# Galileo_Control_Board.net
KiCad netlist of a schematic drawn in Altium Designer
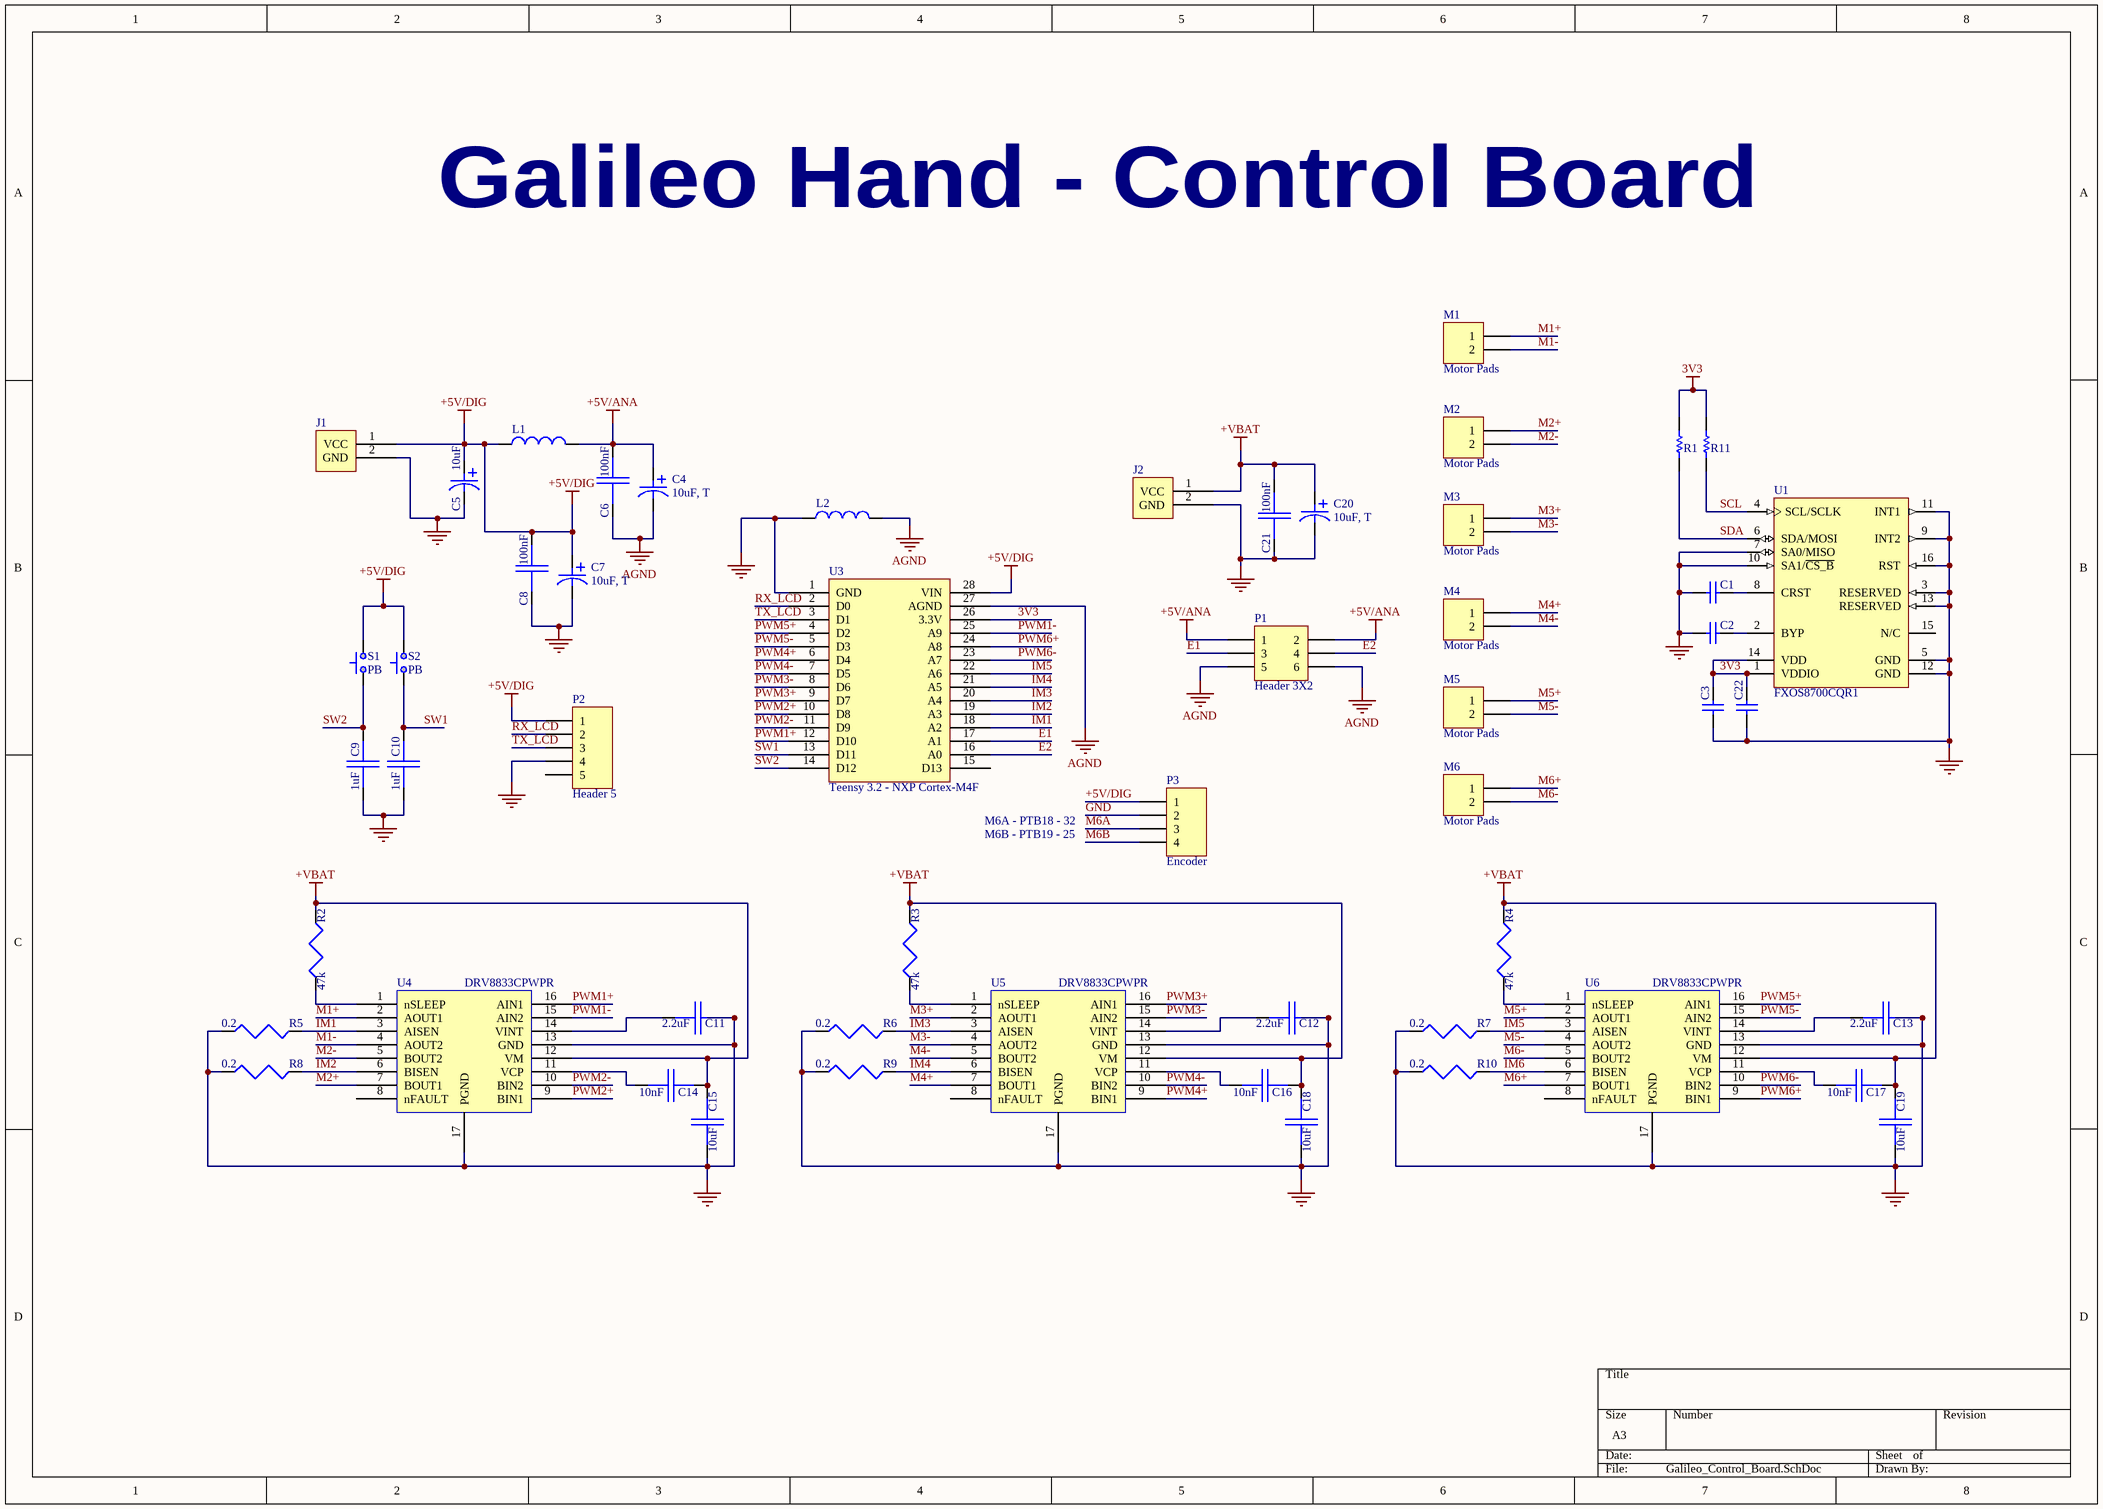
[diagram p0: Galileo_Control_Board.SchDoc]

(export (version "E")
  (design (tool "Eeschema 10.0.6"))
  (components
    (comp (ref "C1")
      (value "GRM155R71C104KA88J")
      (footprint "CAPC1005X55X25LL05T10")
      (fields (field (name "MANUFACTURER") "Murata"))
      (libsource (lib "Altium Content Vault") (part "CMP-2008-03928-1"))
    )
    (comp (ref "C2")
      (value "GRM155R71C104KA88J")
      (footprint "CAPC1005X55X25LL05T10")
      (fields (field (name "MANUFACTURER") "Murata"))
      (libsource (lib "Altium Content Vault") (part "CMP-2008-03928-1"))
    )
    (comp (ref "C3")
      (value "GRM155R60J475ME47D")
      (footprint "CAPC1005X55X25NL05T10")
      (fields (field (name "MANUFACTURER") "Murata"))
      (libsource (lib "Altium Content Vault") (part "CAP"))
    )
    (comp (ref "C4")
      (value "10uF, T")
      (footprint "C1206")
      (description "CAP TANT 10UF 20V 10% 2413")
      (fields
        (field (name "MANUFACTURER") "Kemet")
        (field (name "MANUFACTURER PART NUMBER") "TCJA106M025R0150")
      )
      (libsource (lib "Control") (part "T491C106K020AT"))
    )
    (comp (ref "C5")
      (value "10uF")
      (footprint "CSVB")
      (description "CAP ALUM 10UF 20% 25V SMD")
      (fields
        (field (name "MANUFACTURER") "Panasonic Electronic Components")
        (field (name "MANUFACTURER PART NUMBER") "EEE-1EA100WR")
      )
      (libsource (lib "Control") (part "EEE-1EA100WR"))
    )
    (comp (ref "C6")
      (value "100nF")
      (footprint "C0603")
      (description "CAP CER 0.1UF 25V X7R 0603")
      (fields
        (field (name "MANUFACTURER") "Murata Electronics North America")
        (field (name "MANUFACTURER PART NUMBER") "GRM188R71E104KA01D")
      )
      (libsource (lib "EMG") (part "GRM188R71E104KA01D"))
    )
    (comp (ref "C7")
      (value "10uF, T")
      (footprint "C1206")
      (description "CAP TANT 10UF 20V 10% 2413")
      (fields
        (field (name "MANUFACTURER") "Kemet")
        (field (name "MANUFACTURER PART NUMBER") "TCJA106M025R0150")
      )
      (libsource (lib "Control") (part "T491C106K020AT"))
    )
    (comp (ref "C8")
      (value "100nF")
      (footprint "C0603")
      (description "CAP CER 0.1UF 25V X7R 0603")
      (fields
        (field (name "MANUFACTURER") "Murata Electronics North America")
        (field (name "MANUFACTURER PART NUMBER") "GRM188R71E104KA01D")
      )
      (libsource (lib "EMG") (part "GRM188R71E104KA01D"))
    )
    (comp (ref "C9")
      (value "1uF")
      (footprint "C0603")
      (description "CAP CER 1UF 25V X5R 0603")
      (fields
        (field (name "MANUFACTURER") "Murata Electronics North America")
        (field (name "MANUFACTURER PART NUMBER") "GRM188R61E105KA12D")
      )
      (libsource (lib "EMG") (part "GRM188R61E105KA12D"))
    )
    (comp (ref "C10")
      (value "1uF")
      (footprint "C0603")
      (description "CAP CER 1UF 25V X5R 0603")
      (fields
        (field (name "MANUFACTURER") "Murata Electronics North America")
        (field (name "MANUFACTURER PART NUMBER") "GRM188R61E105KA12D")
      )
      (libsource (lib "EMG") (part "GRM188R61E105KA12D"))
    )
    (comp (ref "C11")
      (value "2.2uF")
      (footprint "C0603")
      (description "CAP CER 2.2UF 6.3V X5R 0603")
      (fields
        (field (name "MANUFACTURER") "AVX Corporation")
        (field (name "MANUFACTURER PART NUMBER") "06036D225KAT2A")
      )
      (libsource (lib "Galileo_Control_Board") (part "06036D225KAT2A"))
    )
    (comp (ref "C12")
      (value "2.2uF")
      (footprint "C0603")
      (description "CAP CER 2.2UF 6.3V X5R 0603")
      (fields
        (field (name "MANUFACTURER") "AVX Corporation")
        (field (name "MANUFACTURER PART NUMBER") "06036D225KAT2A")
      )
      (libsource (lib "Galileo_Control_Board") (part "06036D225KAT2A"))
    )
    (comp (ref "C13")
      (value "2.2uF")
      (footprint "C0603")
      (description "CAP CER 2.2UF 6.3V X5R 0603")
      (fields
        (field (name "MANUFACTURER") "AVX Corporation")
        (field (name "MANUFACTURER PART NUMBER") "06036D225KAT2A")
      )
      (libsource (lib "Galileo_Control_Board") (part "06036D225KAT2A"))
    )
    (comp (ref "C14")
      (value "10nF")
      (footprint "C0603")
      (description "CAP CER 10000PF 16V X7R 0603")
      (fields
        (field (name "MANUFACTURER") "Kemet")
        (field (name "MANUFACTURER PART NUMBER") "C0603C103K4RACTU")
      )
      (libsource (lib "Galileo_Control_Board") (part "C0603C103K4RACTU"))
    )
    (comp (ref "C15")
      (value "10uF")
      (footprint "C0603")
      (description "CAP CER 10UF 25V X5R 0603")
      (fields
        (field (name "MANUFACTURER") "Murata Electronics North America")
        (field (name "MANUFACTURER PART NUMBER") "GRT188R61E106ME13D")
      )
      (libsource (lib "Galileo_Control_Board") (part "GRT188R61E106ME13D"))
    )
    (comp (ref "C16")
      (value "10nF")
      (footprint "C0603")
      (description "CAP CER 10000PF 16V X7R 0603")
      (fields
        (field (name "MANUFACTURER") "Kemet")
        (field (name "MANUFACTURER PART NUMBER") "C0603C103K4RACTU")
      )
      (libsource (lib "Galileo_Control_Board") (part "C0603C103K4RACTU"))
    )
    (comp (ref "C17")
      (value "10nF")
      (footprint "C0603")
      (description "CAP CER 10000PF 16V X7R 0603")
      (fields
        (field (name "MANUFACTURER") "Kemet")
        (field (name "MANUFACTURER PART NUMBER") "C0603C103K4RACTU")
      )
      (libsource (lib "Galileo_Control_Board") (part "C0603C103K4RACTU"))
    )
    (comp (ref "C18")
      (value "10uF")
      (footprint "C0603")
      (description "CAP CER 10UF 25V X5R 0603")
      (fields
        (field (name "MANUFACTURER") "Murata Electronics North America")
        (field (name "MANUFACTURER PART NUMBER") "GRT188R61E106ME13D")
      )
      (libsource (lib "Galileo_Control_Board") (part "GRT188R61E106ME13D"))
    )
    (comp (ref "C19")
      (value "10uF")
      (footprint "C0603")
      (description "CAP CER 10UF 25V X5R 0603")
      (fields
        (field (name "MANUFACTURER") "Murata Electronics North America")
        (field (name "MANUFACTURER PART NUMBER") "GRT188R61E106ME13D")
      )
      (libsource (lib "Galileo_Control_Board") (part "GRT188R61E106ME13D"))
    )
    (comp (ref "C20")
      (value "10uF, T")
      (footprint "C1206")
      (description "CAP TANT 10UF 20V 10% 2413")
      (fields
        (field (name "MANUFACTURER") "Kemet")
        (field (name "MANUFACTURER PART NUMBER") "TCJA106M025R0150")
      )
      (libsource (lib "Control") (part "T491C106K020AT"))
    )
    (comp (ref "C21")
      (value "100nF")
      (footprint "C0603")
      (description "CAP CER 0.1UF 25V X7R 0603")
      (fields
        (field (name "MANUFACTURER") "Murata Electronics North America")
        (field (name "MANUFACTURER PART NUMBER") "GRM188R71E104KA01D")
      )
      (libsource (lib "EMG") (part "GRM188R71E104KA01D"))
    )
    (comp (ref "C22")
      (value "GRM155R71C104KA88J")
      (footprint "CAPC1005X55X25LL05T10")
      (fields (field (name "MANUFACTURER") "Murata"))
      (libsource (lib "Altium Content Vault") (part "CMP-2008-03928-1"))
    )
    (comp (ref "J1")
      (value "TERMINAL BLOCK  2POS 3.5MM")
      (footprint "2POS3.5mm")
      (description "CONN TERMINAL BLOCK 2POS 3.5MM")
      (fields
        (field (name "MANUFACTURER") "Molex, LLC")
        (field (name "MANUFACTURER PART NUMBER") "0393570002")
      )
      (libsource (lib "Control") (part "0393570002"))
    )
    (comp (ref "J2")
      (value "TERMINAL BLOCK  2POS 3.5MM")
      (footprint "2POS3.5mm")
      (description "CONN TERMINAL BLOCK 2POS 3.5MM")
      (fields
        (field (name "MANUFACTURER") "Molex, LLC")
        (field (name "MANUFACTURER PART NUMBER") "0393570002")
      )
      (libsource (lib "Control") (part "0393570002"))
    )
    (comp (ref "L1")
      (value "EMI FILTER BED")
      (footprint "R0603")
      (description "FERRITE BEAD 470 OHM 0603")
      (fields
        (field (name "MANUFACTURER") "Murata Electronics North America")
        (field (name "MANUFACTURER PART NUMBER") "BLM18PG471SN1D")
      )
      (libsource (lib "Control") (part "BLM18PG471SN1D"))
    )
    (comp (ref "L2")
      (value "EMI FILTER BED")
      (footprint "R0603")
      (description "FERRITE BEAD 470 OHM 0603")
      (fields
        (field (name "MANUFACTURER") "Murata Electronics North America")
        (field (name "MANUFACTURER PART NUMBER") "BLM18PG471SN1D")
      )
      (libsource (lib "Control") (part "BLM18PG471SN1D"))
    )
    (comp (ref "M1")
      (value "Motor Pads")
      (footprint "HDR1X2")
      (description "Header, 2-Pin")
      (fields (field (name "PUBLISHER") "Altium Limited"))
      (libsource (lib "Miscellaneous Connectors") (part "Header 2"))
    )
    (comp (ref "M2")
      (value "Motor Pads")
      (footprint "HDR1X2")
      (description "Header, 2-Pin")
      (fields (field (name "PUBLISHER") "Altium Limited"))
      (libsource (lib "Miscellaneous Connectors") (part "Header 2"))
    )
    (comp (ref "M3")
      (value "Motor Pads")
      (footprint "HDR1X2")
      (description "Header, 2-Pin")
      (fields (field (name "PUBLISHER") "Altium Limited"))
      (libsource (lib "Miscellaneous Connectors") (part "Header 2"))
    )
    (comp (ref "M4")
      (value "Motor Pads")
      (footprint "HDR1X2")
      (description "Header, 2-Pin")
      (fields (field (name "PUBLISHER") "Altium Limited"))
      (libsource (lib "Miscellaneous Connectors") (part "Header 2"))
    )
    (comp (ref "M5")
      (value "Motor Pads")
      (footprint "HDR1X2")
      (description "Header, 2-Pin")
      (fields (field (name "PUBLISHER") "Altium Limited"))
      (libsource (lib "Miscellaneous Connectors") (part "Header 2"))
    )
    (comp (ref "M6")
      (value "Motor Pads")
      (footprint "HDR1X2")
      (description "Header, 2-Pin")
      (fields (field (name "PUBLISHER") "Altium Limited"))
      (libsource (lib "Miscellaneous Connectors") (part "Header 2"))
    )
    (comp (ref "P1")
      (value "Header 3X2")
      (footprint "HDR2X3")
      (description "Header, 3-Pin, Dual row")
      (fields (field (name "PUBLISHER") "Altium Limited"))
      (libsource (lib "Miscellaneous Connectors") (part "Header 3X2"))
    )
    (comp (ref "P2")
      (value "Header 5")
      (footprint "HDR1X5")
      (description "Header, 5-Pin")
      (fields (field (name "PUBLISHER") "Altium Limited"))
      (libsource (lib "Miscellaneous Connectors") (part "Header 5"))
    )
    (comp (ref "P3")
      (value "Encoder")
      (footprint "HDR1X4")
      (description "Header, 4-Pin")
      (fields (field (name "PUBLISHER") "Altium Limited"))
      (libsource (lib "Miscellaneous Connectors") (part "Header 4"))
    )
    (comp (ref "R1")
      (value "ERA-2AED472X")
      (footprint "RESC1005X40X25NL10T10")
      (fields (field (name "MANUFACTURER") "Panasonic"))
      (libsource (lib "Altium Content Vault") (part "CMP-2002-05861-1"))
    )
    (comp (ref "R2")
      (value "47k")
      (footprint "R0603")
      (description "RES SMD 47K OHM 1% 1/10W 0603")
      (fields
        (field (name "MANUFACTURER") "Panasonic Electronic Components")
        (field (name "MANUFACTURER PART NUMBER") "ERJ-3EKF4702V")
      )
      (libsource (lib "Galileo_Control_Board") (part "ERJ-3EKF4702V"))
    )
    (comp (ref "R3")
      (value "47k")
      (footprint "R0603")
      (description "RES SMD 47K OHM 1% 1/10W 0603")
      (fields
        (field (name "MANUFACTURER") "Panasonic Electronic Components")
        (field (name "MANUFACTURER PART NUMBER") "ERJ-3EKF4702V")
      )
      (libsource (lib "Galileo_Control_Board") (part "ERJ-3EKF4702V"))
    )
    (comp (ref "R4")
      (value "47k")
      (footprint "R0603")
      (description "RES SMD 47K OHM 1% 1/10W 0603")
      (fields
        (field (name "MANUFACTURER") "Panasonic Electronic Components")
        (field (name "MANUFACTURER PART NUMBER") "ERJ-3EKF4702V")
      )
      (libsource (lib "Galileo_Control_Board") (part "ERJ-3EKF4702V"))
    )
    (comp (ref "R5")
      (value "0.2")
      (footprint "R1206")
      (description "RES SMD 0.2 OHM 5% 1/2W 1206")
      (fields
        (field (name "MANUFACTURER") "Panasonic Electronic Components")
        (field (name "MANUFACTURER PART NUMBER") "ERJ-8BSJR20V")
      )
      (libsource (lib "Galileo_Control_Board") (part "ERJ-8BSJR20V"))
    )
    (comp (ref "R6")
      (value "0.2")
      (footprint "R1206")
      (description "RES SMD 0.2 OHM 5% 1/2W 1206")
      (fields
        (field (name "MANUFACTURER") "Panasonic Electronic Components")
        (field (name "MANUFACTURER PART NUMBER") "ERJ-8BSJR20V")
      )
      (libsource (lib "Galileo_Control_Board") (part "ERJ-8BSJR20V"))
    )
    (comp (ref "R7")
      (value "0.2")
      (footprint "R1206")
      (description "RES SMD 0.2 OHM 5% 1/2W 1206")
      (fields
        (field (name "MANUFACTURER") "Panasonic Electronic Components")
        (field (name "MANUFACTURER PART NUMBER") "ERJ-8BSJR20V")
      )
      (libsource (lib "Galileo_Control_Board") (part "ERJ-8BSJR20V"))
    )
    (comp (ref "R8")
      (value "0.2")
      (footprint "R1206")
      (description "RES SMD 0.2 OHM 5% 1/2W 1206")
      (fields
        (field (name "MANUFACTURER") "Panasonic Electronic Components")
        (field (name "MANUFACTURER PART NUMBER") "ERJ-8BSJR20V")
      )
      (libsource (lib "Galileo_Control_Board") (part "ERJ-8BSJR20V"))
    )
    (comp (ref "R9")
      (value "0.2")
      (footprint "R1206")
      (description "RES SMD 0.2 OHM 5% 1/2W 1206")
      (fields
        (field (name "MANUFACTURER") "Panasonic Electronic Components")
        (field (name "MANUFACTURER PART NUMBER") "ERJ-8BSJR20V")
      )
      (libsource (lib "Galileo_Control_Board") (part "ERJ-8BSJR20V"))
    )
    (comp (ref "R10")
      (value "0.2")
      (footprint "R1206")
      (description "RES SMD 0.2 OHM 5% 1/2W 1206")
      (fields
        (field (name "MANUFACTURER") "Panasonic Electronic Components")
        (field (name "MANUFACTURER PART NUMBER") "ERJ-8BSJR20V")
      )
      (libsource (lib "Galileo_Control_Board") (part "ERJ-8BSJR20V"))
    )
    (comp (ref "R11")
      (value "ERA-2AED472X")
      (footprint "RESC1005X40X25NL10T10")
      (fields (field (name "MANUFACTURER") "Panasonic"))
      (libsource (lib "Altium Content Vault") (part "CMP-2002-05861-1"))
    )
    (comp (ref "S1")
      (value "PB")
      (footprint "SW")
      (description "SWITCH PUSH SPST-NO 0.1A 32V")
      (fields
        (field (name "MANUFACTURER") "C&K Components")
        (field (name "MANUFACTURER PART NUMBER") "D6C90 F1 LFS")
      )
      (libsource (lib "Control") (part "D6C90 F1 LFS"))
    )
    (comp (ref "S2")
      (value "PB")
      (footprint "SW")
      (description "SWITCH PUSH SPST-NO 0.1A 32V")
      (fields
        (field (name "MANUFACTURER") "C&K Components")
        (field (name "MANUFACTURER PART NUMBER") "D6C90 F1 LFS")
      )
      (libsource (lib "Control") (part "D6C90 F1 LFS"))
    )
    (comp (ref "U1")
      (value "FXOS8700CQR1")
      (footprint "FREE-QFN-16-3000X3000DE_V")
      (fields (field (name "MANUFACTURER") "Freescale"))
      (libsource (lib "Altium Content Vault") (part "FREE-FXOS8700CQR1-16"))
    )
    (comp (ref "U3")
      (value "Teensy 3.2 - NXP Cortex-M4F")
      (footprint "DIP28")
      (fields
        (field (name "MANUFACTURER") "SparkFun Electronics")
        (field (name "MANUFACTURER PART NUMBER") "DEV-13305")
      )
      (libsource (lib "Galileo_Control_Board_Library") (part "Teensy"))
    )
    (comp (ref "U4")
      (value "DRV8833CPWPR")
      (footprint "SOP16")
      (description "IC MOTOR DRIVER PAR")
      (fields (field (name "MANUFACTURER") "Texas Instruments"))
      (libsource (lib "Galileo_Control_Board") (part "DRV8833CPWPR"))
    )
    (comp (ref "U5")
      (value "DRV8833CPWPR")
      (footprint "SOP16")
      (description "IC MOTOR DRIVER PAR")
      (fields (field (name "MANUFACTURER") "Texas Instruments"))
      (libsource (lib "Galileo_Control_Board") (part "DRV8833CPWPR"))
    )
    (comp (ref "U6")
      (value "DRV8833CPWPR")
      (footprint "SOP16")
      (description "IC MOTOR DRIVER PAR")
      (fields (field (name "MANUFACTURER") "Texas Instruments"))
      (libsource (lib "Galileo_Control_Board") (part "DRV8833CPWPR"))
    )
  )
  (nets
    (net (code "1") (name "+5V{slash}ANA") (class "Default")
      (node (ref "C4") (pin "1") (pinfunction "1_1") (pintype "passive"))
      (node (ref "C6") (pin "2") (pinfunction "2_2") (pintype "passive"))
      (node (ref "L1") (pin "2") (pinfunction "2_2") (pintype "passive"))
      (node (ref "P1") (pin "1") (pinfunction "1_1") (pintype "passive"))
      (node (ref "P1") (pin "2") (pinfunction "2_2") (pintype "passive"))
    )
    (net (code "2") (name "+5V{slash}DIG") (class "Default")
      (node (ref "C5") (pin "1") (pinfunction "1_1") (pintype "passive"))
      (node (ref "C7") (pin "1") (pinfunction "1_1") (pintype "passive"))
      (node (ref "C8") (pin "2") (pinfunction "2_2") (pintype "passive"))
      (node (ref "J1") (pin "1") (pinfunction "VCC_1") (pintype "passive"))
      (node (ref "L1") (pin "1") (pinfunction "1_1") (pintype "passive"))
      (node (ref "P2") (pin "1") (pinfunction "1_1") (pintype "passive"))
      (node (ref "P3") (pin "1") (pinfunction "1_1") (pintype "passive"))
      (node (ref "S1") (pin "2") (pinfunction "2_2") (pintype "passive"))
      (node (ref "S2") (pin "2") (pinfunction "2_2") (pintype "passive"))
      (node (ref "U3") (pin "28") (pinfunction "VIN_28") (pintype "passive"))
    )
    (net (code "3") (name "+VBAT") (class "Default")
      (node (ref "C14") (pin "2") (pinfunction "2_2") (pintype "passive"))
      (node (ref "C15") (pin "2") (pinfunction "2_2") (pintype "passive"))
      (node (ref "C16") (pin "2") (pinfunction "2_2") (pintype "passive"))
      (node (ref "C17") (pin "2") (pinfunction "2_2") (pintype "passive"))
      (node (ref "C18") (pin "2") (pinfunction "2_2") (pintype "passive"))
      (node (ref "C19") (pin "2") (pinfunction "2_2") (pintype "passive"))
      (node (ref "C20") (pin "1") (pinfunction "1_1") (pintype "passive"))
      (node (ref "C21") (pin "2") (pinfunction "2_2") (pintype "passive"))
      (node (ref "J2") (pin "1") (pinfunction "VCC_1") (pintype "passive"))
      (node (ref "R2") (pin "2") (pinfunction "2_2") (pintype "passive"))
      (node (ref "R3") (pin "2") (pinfunction "2_2") (pintype "passive"))
      (node (ref "R4") (pin "2") (pinfunction "2_2") (pintype "passive"))
      (node (ref "U4") (pin "12") (pinfunction "VM_12") (pintype "passive"))
      (node (ref "U5") (pin "12") (pinfunction "VM_12") (pintype "passive"))
      (node (ref "U6") (pin "12") (pinfunction "VM_12") (pintype "passive"))
    )
    (net (code "4") (name "/E1") (class "Default")
      (node (ref "P1") (pin "3") (pinfunction "3_3") (pintype "passive"))
      (node (ref "U3") (pin "17") (pinfunction "A1_17") (pintype "passive"))
    )
    (net (code "5") (name "/E2") (class "Default")
      (node (ref "P1") (pin "4") (pinfunction "4_4") (pintype "passive"))
      (node (ref "U3") (pin "16") (pinfunction "A0_16") (pintype "passive"))
    )
    (net (code "6") (name "/IM1") (class "Default")
      (node (ref "R5") (pin "2") (pinfunction "2_2") (pintype "passive"))
      (node (ref "U3") (pin "18") (pinfunction "A2_18") (pintype "passive"))
      (node (ref "U4") (pin "3") (pinfunction "AISEN_3") (pintype "passive"))
    )
    (net (code "7") (name "/IM2") (class "Default")
      (node (ref "R8") (pin "2") (pinfunction "2_2") (pintype "passive"))
      (node (ref "U3") (pin "19") (pinfunction "A3_19") (pintype "passive"))
      (node (ref "U4") (pin "6") (pinfunction "BISEN_6") (pintype "passive"))
    )
    (net (code "8") (name "/IM3") (class "Default")
      (node (ref "R6") (pin "2") (pinfunction "2_2") (pintype "passive"))
      (node (ref "U3") (pin "20") (pinfunction "A4_20") (pintype "passive"))
      (node (ref "U5") (pin "3") (pinfunction "AISEN_3") (pintype "passive"))
    )
    (net (code "9") (name "/IM4") (class "Default")
      (node (ref "R9") (pin "2") (pinfunction "2_2") (pintype "passive"))
      (node (ref "U3") (pin "21") (pinfunction "A5_21") (pintype "passive"))
      (node (ref "U5") (pin "6") (pinfunction "BISEN_6") (pintype "passive"))
    )
    (net (code "10") (name "/IM5") (class "Default")
      (node (ref "R7") (pin "2") (pinfunction "2_2") (pintype "passive"))
      (node (ref "U3") (pin "22") (pinfunction "A6_22") (pintype "passive"))
      (node (ref "U6") (pin "3") (pinfunction "AISEN_3") (pintype "passive"))
    )
    (net (code "11") (name "/IM6") (class "Default")
      (node (ref "R10") (pin "2") (pinfunction "2_2") (pintype "passive"))
      (node (ref "U6") (pin "6") (pinfunction "BISEN_6") (pintype "passive"))
    )
    (net (code "12") (name "/M1+") (class "Default")
      (node (ref "M1") (pin "1") (pinfunction "1_1") (pintype "passive"))
      (node (ref "U4") (pin "2") (pinfunction "AOUT1_2") (pintype "passive"))
    )
    (net (code "13") (name "/M1-") (class "Default")
      (node (ref "M1") (pin "2") (pinfunction "2_2") (pintype "passive"))
      (node (ref "U4") (pin "4") (pinfunction "AOUT2_4") (pintype "passive"))
    )
    (net (code "14") (name "/M2+") (class "Default")
      (node (ref "M2") (pin "1") (pinfunction "1_1") (pintype "passive"))
      (node (ref "U4") (pin "7") (pinfunction "BOUT1_7") (pintype "passive"))
    )
    (net (code "15") (name "/M2-") (class "Default")
      (node (ref "M2") (pin "2") (pinfunction "2_2") (pintype "passive"))
      (node (ref "U4") (pin "5") (pinfunction "BOUT2_5") (pintype "passive"))
    )
    (net (code "16") (name "/M3+") (class "Default")
      (node (ref "M3") (pin "1") (pinfunction "1_1") (pintype "passive"))
      (node (ref "U5") (pin "2") (pinfunction "AOUT1_2") (pintype "passive"))
    )
    (net (code "17") (name "/M3-") (class "Default")
      (node (ref "M3") (pin "2") (pinfunction "2_2") (pintype "passive"))
      (node (ref "U5") (pin "4") (pinfunction "AOUT2_4") (pintype "passive"))
    )
    (net (code "18") (name "/M4+") (class "Default")
      (node (ref "M4") (pin "1") (pinfunction "1_1") (pintype "passive"))
      (node (ref "U5") (pin "7") (pinfunction "BOUT1_7") (pintype "passive"))
    )
    (net (code "19") (name "/M4-") (class "Default")
      (node (ref "M4") (pin "2") (pinfunction "2_2") (pintype "passive"))
      (node (ref "U5") (pin "5") (pinfunction "BOUT2_5") (pintype "passive"))
    )
    (net (code "20") (name "/M5+") (class "Default")
      (node (ref "M5") (pin "1") (pinfunction "1_1") (pintype "passive"))
      (node (ref "U6") (pin "2") (pinfunction "AOUT1_2") (pintype "passive"))
    )
    (net (code "21") (name "/M5-") (class "Default")
      (node (ref "M5") (pin "2") (pinfunction "2_2") (pintype "passive"))
      (node (ref "U6") (pin "4") (pinfunction "AOUT2_4") (pintype "passive"))
    )
    (net (code "22") (name "/M6+") (class "Default")
      (node (ref "M6") (pin "1") (pinfunction "1_1") (pintype "passive"))
      (node (ref "U6") (pin "7") (pinfunction "BOUT1_7") (pintype "passive"))
    )
    (net (code "23") (name "/M6-") (class "Default")
      (node (ref "M6") (pin "2") (pinfunction "2_2") (pintype "passive"))
      (node (ref "U6") (pin "5") (pinfunction "BOUT2_5") (pintype "passive"))
    )
    (net (code "24") (name "/M6A") (class "Default")
      (node (ref "P3") (pin "3") (pinfunction "3_3") (pintype "passive"))
    )
    (net (code "25") (name "/M6B") (class "Default")
      (node (ref "P3") (pin "4") (pinfunction "4_4") (pintype "passive"))
    )
    (net (code "26") (name "/PWM1+") (class "Default")
      (node (ref "U3") (pin "12") (pinfunction "D10_12") (pintype "passive"))
      (node (ref "U4") (pin "16") (pinfunction "AIN1_16") (pintype "passive"))
    )
    (net (code "27") (name "/PWM1-") (class "Default")
      (node (ref "U3") (pin "25") (pinfunction "A9_25") (pintype "passive"))
      (node (ref "U4") (pin "15") (pinfunction "AIN2_15") (pintype "passive"))
    )
    (net (code "28") (name "/PWM2+") (class "Default")
      (node (ref "U3") (pin "10") (pinfunction "D8_10") (pintype "passive"))
      (node (ref "U4") (pin "9") (pinfunction "BIN1_9") (pintype "passive"))
    )
    (net (code "29") (name "/PWM2-") (class "Default")
      (node (ref "U3") (pin "11") (pinfunction "D9_11") (pintype "passive"))
      (node (ref "U4") (pin "10") (pinfunction "BIN2_10") (pintype "passive"))
    )
    (net (code "30") (name "/PWM3+") (class "Default")
      (node (ref "U3") (pin "9") (pinfunction "D7_9") (pintype "passive"))
      (node (ref "U5") (pin "16") (pinfunction "AIN1_16") (pintype "passive"))
    )
    (net (code "31") (name "/PWM3-") (class "Default")
      (node (ref "U3") (pin "8") (pinfunction "D6_8") (pintype "passive"))
      (node (ref "U5") (pin "15") (pinfunction "AIN2_15") (pintype "passive"))
    )
    (net (code "32") (name "/PWM4+") (class "Default")
      (node (ref "U3") (pin "6") (pinfunction "D4_6") (pintype "passive"))
      (node (ref "U5") (pin "9") (pinfunction "BIN1_9") (pintype "passive"))
    )
    (net (code "33") (name "/PWM4-") (class "Default")
      (node (ref "U3") (pin "7") (pinfunction "D5_7") (pintype "passive"))
      (node (ref "U5") (pin "10") (pinfunction "BIN2_10") (pintype "passive"))
    )
    (net (code "34") (name "/PWM5+") (class "Default")
      (node (ref "U3") (pin "4") (pinfunction "D2_4") (pintype "passive"))
      (node (ref "U6") (pin "16") (pinfunction "AIN1_16") (pintype "passive"))
    )
    (net (code "35") (name "/PWM5-") (class "Default")
      (node (ref "U3") (pin "5") (pinfunction "D3_5") (pintype "passive"))
      (node (ref "U6") (pin "15") (pinfunction "AIN2_15") (pintype "passive"))
    )
    (net (code "36") (name "/PWM6+") (class "Default")
      (node (ref "U3") (pin "24") (pinfunction "A8_24") (pintype "passive"))
      (node (ref "U6") (pin "9") (pinfunction "BIN1_9") (pintype "passive"))
    )
    (net (code "37") (name "/PWM6-") (class "Default")
      (node (ref "U3") (pin "23") (pinfunction "A7_23") (pintype "passive"))
      (node (ref "U6") (pin "10") (pinfunction "BIN2_10") (pintype "passive"))
    )
    (net (code "38") (name "/RX_LCD") (class "Default")
      (node (ref "P2") (pin "2") (pinfunction "2_2") (pintype "passive"))
      (node (ref "U3") (pin "2") (pinfunction "D0_2") (pintype "passive"))
    )
    (net (code "39") (name "/SCL") (class "Default")
      (node (ref "R11") (pin "1") (pinfunction "1_1") (pintype "passive"))
      (node (ref "U1") (pin "4") (pinfunction "SCL/SCLK_4") (pintype "input"))
    )
    (net (code "40") (name "/SDA") (class "Default")
      (node (ref "R1") (pin "1") (pinfunction "1_1") (pintype "passive"))
      (node (ref "U1") (pin "6") (pinfunction "SDA/MOSI_6") (pintype "bidirectional"))
    )
    (net (code "41") (name "/SW1") (class "Default")
      (node (ref "C10") (pin "2") (pinfunction "2_2") (pintype "passive"))
      (node (ref "S2") (pin "1") (pinfunction "1_1") (pintype "passive"))
      (node (ref "U3") (pin "13") (pinfunction "D11_13") (pintype "passive"))
    )
    (net (code "42") (name "/SW2") (class "Default")
      (node (ref "C9") (pin "2") (pinfunction "2_2") (pintype "passive"))
      (node (ref "S1") (pin "1") (pinfunction "1_1") (pintype "passive"))
      (node (ref "U3") (pin "14") (pinfunction "D12_14") (pintype "passive"))
    )
    (net (code "43") (name "/TX_LCD") (class "Default")
      (node (ref "P2") (pin "3") (pinfunction "3_3") (pintype "passive"))
      (node (ref "U3") (pin "3") (pinfunction "D1_3") (pintype "passive"))
    )
    (net (code "44") (name "3V3") (class "Default")
      (node (ref "C22") (pin "2") (pinfunction "2_2") (pintype "passive"))
      (node (ref "C3") (pin "2") (pinfunction "2_2") (pintype "passive"))
      (node (ref "R1") (pin "2") (pinfunction "2_2") (pintype "passive"))
      (node (ref "R11") (pin "2") (pinfunction "2_2") (pintype "passive"))
      (node (ref "U1") (pin "1") (pinfunction "VDDIO_1") (pintype "power_in"))
      (node (ref "U1") (pin "14") (pinfunction "VDD_14") (pintype "power_in"))
      (node (ref "U3") (pin "26") (pinfunction "3.3V_26") (pintype "passive"))
    )
    (net (code "45") (name "AGND") (class "Default")
      (node (ref "C4") (pin "2") (pinfunction "2_2") (pintype "passive"))
      (node (ref "C6") (pin "1") (pinfunction "1_1") (pintype "passive"))
      (node (ref "L2") (pin "2") (pinfunction "2_2") (pintype "passive"))
      (node (ref "P1") (pin "5") (pinfunction "5_5") (pintype "passive"))
      (node (ref "P1") (pin "6") (pinfunction "6_6") (pintype "passive"))
      (node (ref "U3") (pin "27") (pinfunction "AGND_27") (pintype "passive"))
    )
    (net (code "46") (name "GND") (class "Default")
      (node (ref "C1") (pin "1") (pinfunction "1_1") (pintype "passive"))
      (node (ref "C10") (pin "1") (pinfunction "1_1") (pintype "passive"))
      (node (ref "C11") (pin "2") (pinfunction "2_2") (pintype "passive"))
      (node (ref "C12") (pin "2") (pinfunction "2_2") (pintype "passive"))
      (node (ref "C13") (pin "2") (pinfunction "2_2") (pintype "passive"))
      (node (ref "C15") (pin "1") (pinfunction "1_1") (pintype "passive"))
      (node (ref "C18") (pin "1") (pinfunction "1_1") (pintype "passive"))
      (node (ref "C19") (pin "1") (pinfunction "1_1") (pintype "passive"))
      (node (ref "C2") (pin "2") (pinfunction "2_2") (pintype "passive"))
      (node (ref "C20") (pin "2") (pinfunction "2_2") (pintype "passive"))
      (node (ref "C21") (pin "1") (pinfunction "1_1") (pintype "passive"))
      (node (ref "C22") (pin "1") (pinfunction "1_1") (pintype "passive"))
      (node (ref "C3") (pin "1") (pinfunction "1_1") (pintype "passive"))
      (node (ref "C5") (pin "2") (pinfunction "2_2") (pintype "passive"))
      (node (ref "C7") (pin "2") (pinfunction "2_2") (pintype "passive"))
      (node (ref "C8") (pin "1") (pinfunction "1_1") (pintype "passive"))
      (node (ref "C9") (pin "1") (pinfunction "1_1") (pintype "passive"))
      (node (ref "J1") (pin "2") (pinfunction "GND_2") (pintype "passive"))
      (node (ref "J2") (pin "2") (pinfunction "GND_2") (pintype "passive"))
      (node (ref "L2") (pin "1") (pinfunction "1_1") (pintype "passive"))
      (node (ref "P2") (pin "4") (pinfunction "4_4") (pintype "passive"))
      (node (ref "P3") (pin "2") (pinfunction "2_2") (pintype "passive"))
      (node (ref "R10") (pin "1") (pinfunction "1_1") (pintype "passive"))
      (node (ref "R5") (pin "1") (pinfunction "1_1") (pintype "passive"))
      (node (ref "R6") (pin "1") (pinfunction "1_1") (pintype "passive"))
      (node (ref "R7") (pin "1") (pinfunction "1_1") (pintype "passive"))
      (node (ref "R8") (pin "1") (pinfunction "1_1") (pintype "passive"))
      (node (ref "R9") (pin "1") (pinfunction "1_1") (pintype "passive"))
      (node (ref "U1") (pin "10") (pinfunction "SA1/~{CS_B}_10") (pintype "input"))
      (node (ref "U1") (pin "11") (pinfunction "INT1_11") (pintype "output"))
      (node (ref "U1") (pin "12") (pinfunction "GND_12") (pintype "power_in"))
      (node (ref "U1") (pin "13") (pinfunction "RESERVED_13") (pintype "input"))
      (node (ref "U1") (pin "16") (pinfunction "RST_16") (pintype "input"))
      (node (ref "U1") (pin "3") (pinfunction "RESERVED_3") (pintype "input"))
      (node (ref "U1") (pin "5") (pinfunction "GND_5") (pintype "power_in"))
      (node (ref "U1") (pin "7") (pinfunction "SA0/MISO_7") (pintype "bidirectional"))
      (node (ref "U1") (pin "9") (pinfunction "INT2_9") (pintype "output"))
      (node (ref "U3") (pin "1") (pinfunction "GND_1") (pintype "passive"))
      (node (ref "U4") (pin "13") (pinfunction "GND_13") (pintype "passive"))
      (node (ref "U4") (pin "17") (pinfunction "PGND_17") (pintype "passive"))
      (node (ref "U5") (pin "13") (pinfunction "GND_13") (pintype "passive"))
      (node (ref "U5") (pin "17") (pinfunction "PGND_17") (pintype "passive"))
      (node (ref "U6") (pin "13") (pinfunction "GND_13") (pintype "passive"))
      (node (ref "U6") (pin "17") (pinfunction "PGND_17") (pintype "passive"))
    )
    (net (code "47") (name "Net-(U1-BYP)") (class "Default")
      (node (ref "C2") (pin "1") (pinfunction "1_1") (pintype "passive"))
      (node (ref "U1") (pin "2") (pinfunction "BYP_2") (pintype "passive"))
    )
    (net (code "48") (name "Net-(U1-CRST)") (class "Default")
      (node (ref "C1") (pin "2") (pinfunction "2_2") (pintype "passive"))
      (node (ref "U1") (pin "8") (pinfunction "CRST_8") (pintype "passive"))
    )
    (net (code "49") (name "Net-(U4-VCP)") (class "Default")
      (node (ref "C14") (pin "1") (pinfunction "1_1") (pintype "passive"))
      (node (ref "U4") (pin "11") (pinfunction "VCP_11") (pintype "passive"))
    )
    (net (code "50") (name "Net-(U4-VINT)") (class "Default")
      (node (ref "C11") (pin "1") (pinfunction "1_1") (pintype "passive"))
      (node (ref "U4") (pin "14") (pinfunction "VINT_14") (pintype "passive"))
    )
    (net (code "51") (name "Net-(U4-nSLEEP)") (class "Default")
      (node (ref "R2") (pin "1") (pinfunction "1_1") (pintype "passive"))
      (node (ref "U4") (pin "1") (pinfunction "nSLEEP_1") (pintype "passive"))
    )
    (net (code "52") (name "Net-(U5-VCP)") (class "Default")
      (node (ref "C16") (pin "1") (pinfunction "1_1") (pintype "passive"))
      (node (ref "U5") (pin "11") (pinfunction "VCP_11") (pintype "passive"))
    )
    (net (code "53") (name "Net-(U5-VINT)") (class "Default")
      (node (ref "C12") (pin "1") (pinfunction "1_1") (pintype "passive"))
      (node (ref "U5") (pin "14") (pinfunction "VINT_14") (pintype "passive"))
    )
    (net (code "54") (name "Net-(U5-nSLEEP)") (class "Default")
      (node (ref "R3") (pin "1") (pinfunction "1_1") (pintype "passive"))
      (node (ref "U5") (pin "1") (pinfunction "nSLEEP_1") (pintype "passive"))
    )
    (net (code "55") (name "Net-(U6-VCP)") (class "Default")
      (node (ref "C17") (pin "1") (pinfunction "1_1") (pintype "passive"))
      (node (ref "U6") (pin "11") (pinfunction "VCP_11") (pintype "passive"))
    )
    (net (code "56") (name "Net-(U6-VINT)") (class "Default")
      (node (ref "C13") (pin "1") (pinfunction "1_1") (pintype "passive"))
      (node (ref "U6") (pin "14") (pinfunction "VINT_14") (pintype "passive"))
    )
    (net (code "57") (name "Net-(U6-nSLEEP)") (class "Default")
      (node (ref "R4") (pin "1") (pinfunction "1_1") (pintype "passive"))
      (node (ref "U6") (pin "1") (pinfunction "nSLEEP_1") (pintype "passive"))
    )
    (net (code "58") (name "unconnected-(P2-Pad5)") (class "Default")
      (node (ref "P2") (pin "5") (pinfunction "5_5") (pintype "passive"))
    )
    (net (code "59") (name "unconnected-(U1-N{slash}C-Pad15)") (class "Default")
      (node (ref "U1") (pin "15") (pinfunction "N/C_15") (pintype "passive"))
    )
    (net (code "60") (name "unconnected-(U3-D13-Pad15)") (class "Default")
      (node (ref "U3") (pin "15") (pinfunction "D13_15") (pintype "passive"))
    )
    (net (code "61") (name "unconnected-(U4-nFAULT-Pad8)") (class "Default")
      (node (ref "U4") (pin "8") (pinfunction "nFAULT_8") (pintype "passive"))
    )
    (net (code "62") (name "unconnected-(U5-nFAULT-Pad8)") (class "Default")
      (node (ref "U5") (pin "8") (pinfunction "nFAULT_8") (pintype "passive"))
    )
    (net (code "63") (name "unconnected-(U6-nFAULT-Pad8)") (class "Default")
      (node (ref "U6") (pin "8") (pinfunction "nFAULT_8") (pintype "passive"))
    )
  )
)
